# Temp_Sensors.net
KiCad netlist of a schematic drawn in Altium Designer
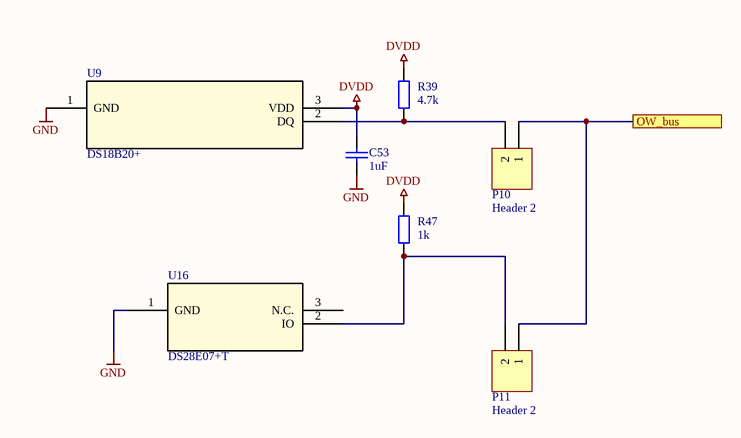
[diagram p0: Temp_Sensors.SchDoc]

(export (version "E")
  (design (tool "Eeschema 10.0.6"))
  (components
    (comp (ref "C53")
      (value "1uF")
      (footprint "C1206-KUE")
      (description "Capacitor")
      (fields (field (name "MANUFACTURER") "Kemet") (field (name "PUBLISHER") "Altium Limited"))
      (libsource (lib "ExtrapartsKUE_V01") (part "Capacitor"))
    )
    (comp (ref "P10")
      (value "Header 2")
      (footprint "HDR1X2")
      (description "Header, 2-Pin")
      (fields (field (name "PUBLISHER") "Altium Limited"))
      (libsource (lib "Miscellaneous Connectors") (part "Header 2"))
    )
    (comp (ref "P11")
      (value "Header 2")
      (footprint "HDR1X2")
      (description "Header, 2-Pin")
      (fields (field (name "PUBLISHER") "Altium Limited"))
      (libsource (lib "Miscellaneous Connectors") (part "Header 2"))
    )
    (comp (ref "R39")
      (value "4.7k")
      (footprint "C1206-KUE")
      (description "Resistor SMD")
      (fields (field (name "MANUFACTURER") "AVX") (field (name "PUBLISHER") "Altium Limited"))
      (libsource (lib "ExtrapartsKUE_V01") (part "ResistorSMD"))
    )
    (comp (ref "R47")
      (value "1k")
      (footprint "C1206-KUE")
      (description "Resistor SMD")
      (fields (field (name "MANUFACTURER") "AVX") (field (name "PUBLISHER") "Altium Limited"))
      (libsource (lib "ExtrapartsKUE_V01") (part "ResistorSMD"))
    )
    (comp (ref "U9")
      (value "DS18B20+")
      (footprint "21-0248A_Q3-1_MXM")
      (description "Programmable Resolution 1-Wire Digital Thermometer")
      (fields (field (name "COPYRIGHT") "Copyright (C) 2025 Ultra Librarian. All rights reserved."))
      (libsource (lib "DS18B20&plus_") (part "DS18B20+"))
    )
    (comp (ref "U16")
      (value "DS28E07+T")
      (footprint "21-0250_Q3+4_MXM")
      (description "1024-Bit, 1-Wire EEPROM")
      (fields (field (name "COPYRIGHT") "Copyright (C) 2026 Ultra Librarian. All rights reserved."))
      (libsource (lib "DS28E07&plus_T") (part "DS28E07+T"))
    )
  )
  (nets
    (net (code "1") (name "/OW_bus") (class "Default")
      (node (ref "P10") (pin "1") (pinfunction "1_1") (pintype "passive"))
      (node (ref "P11") (pin "1") (pinfunction "1_1") (pintype "passive"))
    )
    (net (code "2") (name "DVDD") (class "Default")
      (node (ref "C53") (pin "2") (pinfunction "2_2") (pintype "passive"))
      (node (ref "R39") (pin "1") (pinfunction "1_1") (pintype "passive"))
      (node (ref "R47") (pin "1") (pinfunction "1_1") (pintype "passive"))
      (node (ref "U9") (pin "3") (pinfunction "VDD_3") (pintype "power_in"))
    )
    (net (code "3") (name "GND") (class "Default")
      (node (ref "C53") (pin "1") (pinfunction "1_1") (pintype "passive"))
      (node (ref "U16") (pin "1") (pinfunction "GND_1") (pintype "power_in"))
      (node (ref "U9") (pin "1") (pinfunction "GND_1") (pintype "power_in"))
    )
    (net (code "4") (name "Net-(U9-DQ)") (class "Default")
      (node (ref "P10") (pin "2") (pinfunction "2_2") (pintype "passive"))
      (node (ref "R39") (pin "2") (pinfunction "2_2") (pintype "passive"))
      (node (ref "U9") (pin "2") (pinfunction "DQ_2") (pintype "passive"))
    )
    (net (code "5") (name "Net-(U16-IO)") (class "Default")
      (node (ref "P11") (pin "2") (pinfunction "2_2") (pintype "passive"))
      (node (ref "R47") (pin "2") (pinfunction "2_2") (pintype "passive"))
      (node (ref "U16") (pin "2") (pinfunction "IO_2") (pintype "passive"))
    )
    (net (code "6") (name "unconnected-(U16-N.C.-Pad3)") (class "Default")
      (node (ref "U16") (pin "3") (pinfunction "N.C._3") (pintype "passive"))
    )
  )
)
